# schema_mixer.net
KiCad netlist of a schematic drawn in Altium Designer
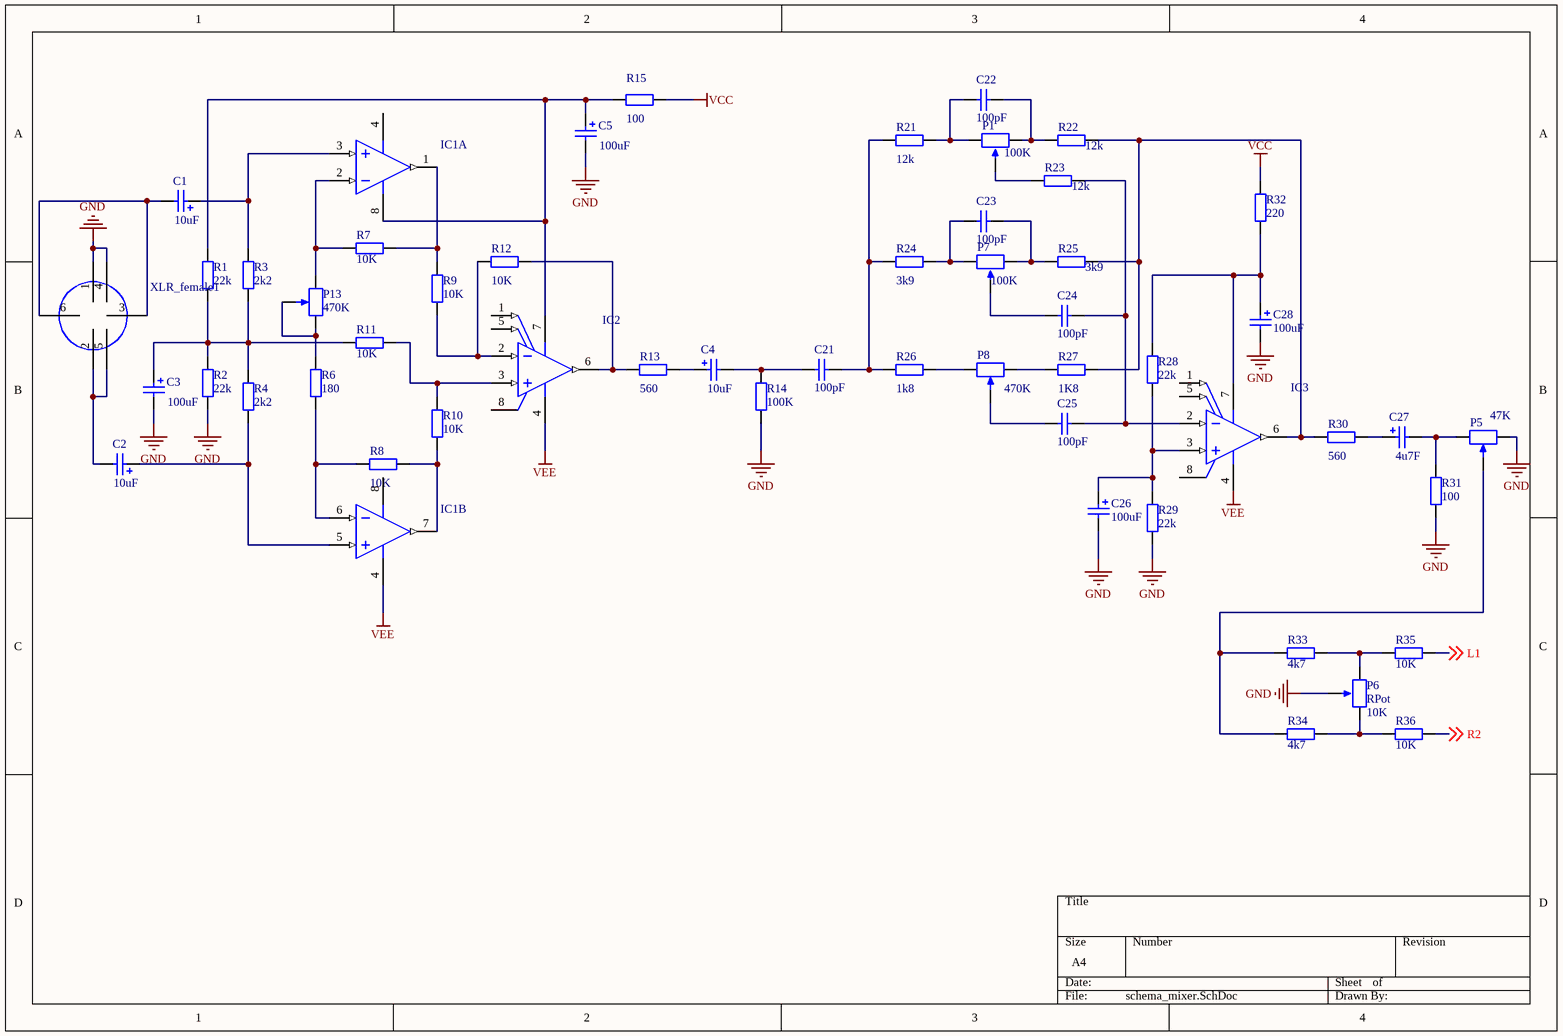
[diagram p0: schema_mixer.SchDoc]

(export (version "E")
  (design (tool "Eeschema 10.0.6"))
  (components
    (comp (ref "C1")
      (value "10uF")
      (footprint "POLAR0.8")
      (description "Polarized Capacitor (Axial)")
      (fields (field (name "Comment") "Cap Pol2") (field (name "PUBLISHER") "Altium Limited"))
      (libsource (lib "Miscellaneous Devices") (part "Cap Pol2"))
    )
    (comp (ref "C2")
      (value "10uF")
      (footprint "POLAR0.8")
      (description "Polarized Capacitor (Axial)")
      (fields (field (name "Comment") "Cap Pol2") (field (name "PUBLISHER") "Altium Limited"))
      (libsource (lib "Miscellaneous Devices") (part "Cap Pol2"))
    )
    (comp (ref "C3")
      (value "100uF")
      (footprint "POLAR0.8")
      (description "Polarized Capacitor (Axial)")
      (fields (field (name "Comment") "Cap Pol2") (field (name "PUBLISHER") "Altium Limited"))
      (libsource (lib "Miscellaneous Devices") (part "Cap Pol2"))
    )
    (comp (ref "C4")
      (value "10uF")
      (footprint "POLAR0.8")
      (description "Polarized Capacitor (Axial)")
      (fields (field (name "Comment") "Cap Pol2") (field (name "PUBLISHER") "Altium Limited"))
      (libsource (lib "Miscellaneous Devices") (part "Cap Pol2"))
    )
    (comp (ref "C5")
      (value "100uF")
      (footprint "POLAR0.8")
      (description "Polarized Capacitor (Axial)")
      (fields (field (name "Comment") "Cap Pol2") (field (name "PUBLISHER") "Altium Limited"))
      (libsource (lib "Miscellaneous Devices") (part "Cap Pol2"))
    )
    (comp (ref "C21")
      (value "100pF")
      (footprint "RAD-0.3")
      (description "Capacitor")
      (fields (field (name "Comment") "Cap") (field (name "PUBLISHER") "Altium Limited"))
      (libsource (lib "Autio_Mixer") (part "Cap"))
    )
    (comp (ref "C22")
      (value "100pF")
      (footprint "RAD-0.3")
      (description "Capacitor")
      (fields (field (name "Comment") "Cap") (field (name "PUBLISHER") "Altium Limited"))
      (libsource (lib "Autio_Mixer") (part "Cap"))
    )
    (comp (ref "C23")
      (value "100pF")
      (footprint "RAD-0.3")
      (description "Capacitor")
      (fields (field (name "Comment") "Cap") (field (name "PUBLISHER") "Altium Limited"))
      (libsource (lib "Autio_Mixer") (part "Cap"))
    )
    (comp (ref "C24")
      (value "100pF")
      (footprint "RAD-0.3")
      (description "Capacitor")
      (fields (field (name "Comment") "Cap") (field (name "PUBLISHER") "Altium Limited"))
      (libsource (lib "Autio_Mixer") (part "Cap"))
    )
    (comp (ref "C25")
      (value "100pF")
      (footprint "RAD-0.3")
      (description "Capacitor")
      (fields (field (name "Comment") "Cap") (field (name "PUBLISHER") "Altium Limited"))
      (libsource (lib "Autio_Mixer") (part "Cap"))
    )
    (comp (ref "C26")
      (value "100uF")
      (footprint "POLAR0.8")
      (description "Polarized Capacitor (Axial)")
      (fields (field (name "Comment") "Cap Pol2") (field (name "PUBLISHER") "Altium Limited"))
      (libsource (lib "Miscellaneous Devices") (part "Cap Pol2"))
    )
    (comp (ref "C27")
      (value "4u7F")
      (footprint "POLAR0.8")
      (description "Polarized Capacitor (Axial)")
      (fields (field (name "Comment") "Cap Pol2") (field (name "PUBLISHER") "Altium Limited"))
      (libsource (lib "Miscellaneous Devices") (part "Cap Pol2"))
    )
    (comp (ref "C28")
      (value "100uF")
      (footprint "POLAR0.8")
      (description "Polarized Capacitor (Axial)")
      (fields (field (name "Comment") "Cap Pol2") (field (name "PUBLISHER") "Altium Limited"))
      (libsource (lib "Miscellaneous Devices") (part "Cap Pol2"))
    )
    (comp (ref "IC1")
      (value "LM833DR2G")
      (footprint "OPAMP_LM833")
      (description "Low Noise, Audio Dual Operational Amplifier, -40 to 85 degC, 8-Pin SOIC, Pb-Free, Tape and Reel")
      (fields (field (name "MANUFACTURER") "On Semiconductor"))
      (libsource (lib "Autio_Mixer") (part "opamp_LM833"))
    )
    (comp (ref "IC2")
      (value "TL061CD")
      (footprint "OPAMP_TL061")
      (fields (field (name "MANUFACTURER") "Texas Instruments"))
      (libsource (lib "Autio_Mixer") (part "opamp_L061"))
    )
    (comp (ref "IC3")
      (value "TL061CD")
      (footprint "OPAMP_TL061")
      (fields (field (name "MANUFACTURER") "Texas Instruments"))
      (libsource (lib "Autio_Mixer") (part "opamp_TL061"))
    )
    (comp (ref "P1")
      (value "100K")
      (footprint "VR5")
      (description "Potentiometer")
      (fields (field (name "Comment") "RPot") (field (name "PUBLISHER") "Altium Limited"))
      (libsource (lib "") (part "RPot_1"))
    )
    (comp (ref "P5")
      (value "47K")
      (footprint "VR5")
      (description "Potentiometer")
      (fields (field (name "Comment") "RPot") (field (name "PUBLISHER") "Altium Limited"))
      (libsource (lib "") (part "RPot_1_1"))
    )
    (comp (ref "P6")
      (value "RPot")
      (footprint "VR5")
      (description "Potentiometer")
      (fields (field (name "ALTIUM_VALUE") "10K") (field (name "PUBLISHER") "Altium Limited"))
      (libsource (lib "Autio_Mixer") (part "RPot"))
    )
    (comp (ref "P7")
      (value "100K")
      (footprint "VR5")
      (description "Potentiometer")
      (fields (field (name "Comment") "RPot") (field (name "PUBLISHER") "Altium Limited"))
      (libsource (lib "") (part "RPot_1"))
    )
    (comp (ref "P8")
      (value "470K")
      (footprint "VR5")
      (description "Potentiometer")
      (fields (field (name "Comment") "RPot") (field (name "PUBLISHER") "Altium Limited"))
      (libsource (lib "") (part "RPot_1_1"))
    )
    (comp (ref "P13")
      (value "470K")
      (footprint "VR5")
      (description "Potentiometer")
      (fields (field (name "Comment") "RPot") (field (name "PUBLISHER") "Altium Limited"))
      (libsource (lib "Autio_Mixer") (part "RPot_1"))
    )
    (comp (ref "R1")
      (value "22k")
      (footprint "C1206")
      (description "Resistor")
      (fields (field (name "Comment") "Res2") (field (name "PUBLISHER") "Altium Limited"))
      (libsource (lib "") (part "Res2_1"))
    )
    (comp (ref "R2")
      (value "22k")
      (footprint "C1206")
      (description "Resistor")
      (fields (field (name "Comment") "Res2") (field (name "PUBLISHER") "Altium Limited"))
      (libsource (lib "") (part "Res2_1"))
    )
    (comp (ref "R3")
      (value "2k2")
      (footprint "C1206")
      (description "Resistor")
      (fields (field (name "Comment") "Res2") (field (name "PUBLISHER") "Altium Limited"))
      (libsource (lib "") (part "Res2_1"))
    )
    (comp (ref "R4")
      (value "2k2")
      (footprint "C1206")
      (description "Resistor")
      (fields (field (name "Comment") "Res2") (field (name "PUBLISHER") "Altium Limited"))
      (libsource (lib "") (part "Res2_1"))
    )
    (comp (ref "R6")
      (value "180")
      (footprint "C1206")
      (description "Resistor")
      (fields (field (name "Comment") "Res2") (field (name "PUBLISHER") "Altium Limited"))
      (libsource (lib "") (part "Res2_1"))
    )
    (comp (ref "R7")
      (value "10K")
      (footprint "C1206")
      (description "Resistor")
      (fields (field (name "Comment") "Res2") (field (name "PUBLISHER") "Altium Limited"))
      (libsource (lib "Miscellaneous Devices") (part "Res2"))
    )
    (comp (ref "R8")
      (value "10K")
      (footprint "C1206")
      (description "Resistor")
      (fields (field (name "Comment") "Res2") (field (name "PUBLISHER") "Altium Limited"))
      (libsource (lib "Miscellaneous Devices") (part "Res2"))
    )
    (comp (ref "R9")
      (value "10K")
      (footprint "C1206")
      (description "Resistor")
      (fields (field (name "Comment") "Res2") (field (name "PUBLISHER") "Altium Limited"))
      (libsource (lib "") (part "Res2_1"))
    )
    (comp (ref "R10")
      (value "10K")
      (footprint "C1206")
      (description "Resistor")
      (fields (field (name "Comment") "Res2") (field (name "PUBLISHER") "Altium Limited"))
      (libsource (lib "") (part "Res2_1"))
    )
    (comp (ref "R11")
      (value "10K")
      (footprint "C1206")
      (description "Resistor")
      (fields (field (name "Comment") "Res2") (field (name "PUBLISHER") "Altium Limited"))
      (libsource (lib "Miscellaneous Devices") (part "Res2"))
    )
    (comp (ref "R12")
      (value "10K")
      (footprint "C1206")
      (description "Resistor")
      (fields (field (name "Comment") "Res2") (field (name "PUBLISHER") "Altium Limited"))
      (libsource (lib "Miscellaneous Devices") (part "Res2"))
    )
    (comp (ref "R13")
      (value "560")
      (footprint "C1206")
      (description "Resistor")
      (fields (field (name "Comment") "Res2") (field (name "PUBLISHER") "Altium Limited"))
      (libsource (lib "Miscellaneous Devices") (part "Res2"))
    )
    (comp (ref "R14")
      (value "100K")
      (footprint "C1206")
      (description "Resistor")
      (fields (field (name "Comment") "Res2") (field (name "PUBLISHER") "Altium Limited"))
      (libsource (lib "") (part "Res2_1"))
    )
    (comp (ref "R15")
      (value "100")
      (footprint "C1206")
      (description "Resistor")
      (fields (field (name "Comment") "Res2") (field (name "PUBLISHER") "Altium Limited"))
      (libsource (lib "Miscellaneous Devices") (part "Res2"))
    )
    (comp (ref "R21")
      (value "12k")
      (footprint "C1206")
      (description "Resistor")
      (fields (field (name "Comment") "Res2") (field (name "PUBLISHER") "Altium Limited"))
      (libsource (lib "Miscellaneous Devices") (part "Res2"))
    )
    (comp (ref "R22")
      (value "12k")
      (footprint "C1206")
      (description "Resistor")
      (fields (field (name "Comment") "Res2") (field (name "PUBLISHER") "Altium Limited"))
      (libsource (lib "Miscellaneous Devices") (part "Res2"))
    )
    (comp (ref "R23")
      (value "12k")
      (footprint "C1206")
      (description "Resistor")
      (fields (field (name "Comment") "Res2") (field (name "PUBLISHER") "Altium Limited"))
      (libsource (lib "Miscellaneous Devices") (part "Res2"))
    )
    (comp (ref "R24")
      (value "3k9")
      (footprint "C1206")
      (description "Resistor")
      (fields (field (name "Comment") "Res2") (field (name "PUBLISHER") "Altium Limited"))
      (libsource (lib "Miscellaneous Devices") (part "Res2"))
    )
    (comp (ref "R25")
      (value "3k9")
      (footprint "C1206")
      (description "Resistor")
      (fields (field (name "Comment") "Res2") (field (name "PUBLISHER") "Altium Limited"))
      (libsource (lib "Miscellaneous Devices") (part "Res2"))
    )
    (comp (ref "R26")
      (value "1k8")
      (footprint "C1206")
      (description "Resistor")
      (fields (field (name "Comment") "Res2") (field (name "PUBLISHER") "Altium Limited"))
      (libsource (lib "Miscellaneous Devices") (part "Res2"))
    )
    (comp (ref "R27")
      (value "1K8")
      (footprint "C1206")
      (description "Resistor")
      (fields (field (name "Comment") "Res2") (field (name "PUBLISHER") "Altium Limited"))
      (libsource (lib "Miscellaneous Devices") (part "Res2"))
    )
    (comp (ref "R28")
      (value "22k")
      (footprint "C1206")
      (description "Resistor")
      (fields (field (name "Comment") "Res2") (field (name "PUBLISHER") "Altium Limited"))
      (libsource (lib "") (part "Res2_1"))
    )
    (comp (ref "R29")
      (value "22k")
      (footprint "C1206")
      (description "Resistor")
      (fields (field (name "Comment") "Res2") (field (name "PUBLISHER") "Altium Limited"))
      (libsource (lib "") (part "Res2_1"))
    )
    (comp (ref "R30")
      (value "560")
      (footprint "C1206")
      (description "Resistor")
      (fields (field (name "Comment") "Res2") (field (name "PUBLISHER") "Altium Limited"))
      (libsource (lib "Miscellaneous Devices") (part "Res2"))
    )
    (comp (ref "R31")
      (value "100")
      (footprint "C1206")
      (description "Resistor")
      (fields (field (name "Comment") "Res2") (field (name "PUBLISHER") "Altium Limited"))
      (libsource (lib "") (part "Res2_1"))
    )
    (comp (ref "R32")
      (value "220")
      (footprint "C1206")
      (description "Resistor")
      (fields (field (name "Comment") "Res2") (field (name "PUBLISHER") "Altium Limited"))
      (libsource (lib "") (part "Res2_1"))
    )
    (comp (ref "R33")
      (value "4k7")
      (footprint "C1206")
      (description "Resistor")
      (fields (field (name "Comment") "Res2") (field (name "PUBLISHER") "Altium Limited"))
      (libsource (lib "Autio_Mixer") (part "Res2_13"))
    )
    (comp (ref "R34")
      (value "4k7")
      (footprint "C1206")
      (description "Resistor")
      (fields (field (name "Comment") "Res2") (field (name "PUBLISHER") "Altium Limited"))
      (libsource (lib "Autio_Mixer") (part "Res2_13"))
    )
    (comp (ref "R35")
      (value "10K")
      (footprint "C1206")
      (description "Resistor")
      (fields (field (name "Comment") "Res2") (field (name "PUBLISHER") "Altium Limited"))
      (libsource (lib "Autio_Mixer") (part "Res2_3"))
    )
    (comp (ref "R36")
      (value "10K")
      (footprint "C1206")
      (description "Resistor")
      (fields (field (name "Comment") "Res2") (field (name "PUBLISHER") "Altium Limited"))
      (libsource (lib "Autio_Mixer") (part "Res2_3"))
    )
    (comp (ref "XLR_female1")
      (value "XLR_female")
      (footprint "XLR_Femail_Neutrik_NCJ6FA-V")
      (libsource (lib "Autio_Mixer") (part "XLR_female"))
    )
  )
  (nets
    (net (code "1") (name "GND") (class "Default")
      (node (ref "C26") (pin "2") (pinfunction "2_2") (pintype "passive"))
      (node (ref "C28") (pin "2") (pinfunction "2_2") (pintype "passive"))
      (node (ref "C3") (pin "2") (pinfunction "2_2") (pintype "passive"))
      (node (ref "C5") (pin "2") (pinfunction "2_2") (pintype "passive"))
      (node (ref "P5") (pin "2") (pinfunction "BOT_2") (pintype "passive"))
      (node (ref "P6") (pin "3") (pinfunction "TAP_3") (pintype "passive"))
      (node (ref "R14") (pin "1") (pinfunction "1_1") (pintype "passive"))
      (node (ref "R2") (pin "1") (pinfunction "1_1") (pintype "passive"))
      (node (ref "R29") (pin "1") (pinfunction "1_1") (pintype "passive"))
      (node (ref "R31") (pin "1") (pinfunction "1_1") (pintype "passive"))
      (node (ref "XLR_female1") (pin "1") (pinfunction "GND_1") (pintype "passive"))
      (node (ref "XLR_female1") (pin "4") (pinfunction "Sleeve_/_GND_4") (pintype "passive"))
    )
    (net (code "2") (name "L1") (class "Default")
      (node (ref "R35") (pin "2") (pinfunction "2_2") (pintype "passive"))
    )
    (net (code "3") (name "Net-(C3-Pad1)") (class "Default")
      (node (ref "C3") (pin "1") (pinfunction "1_1") (pintype "passive"))
      (node (ref "R1") (pin "1") (pinfunction "1_1") (pintype "passive"))
      (node (ref "R11") (pin "1") (pinfunction "1_1") (pintype "passive"))
      (node (ref "R2") (pin "2") (pinfunction "2_2") (pintype "passive"))
      (node (ref "R3") (pin "1") (pinfunction "1_1") (pintype "passive"))
      (node (ref "R4") (pin "2") (pinfunction "2_2") (pintype "passive"))
    )
    (net (code "4") (name "Net-(C4-Pad1)") (class "Default")
      (node (ref "C4") (pin "1") (pinfunction "1_1") (pintype "passive"))
      (node (ref "R13") (pin "2") (pinfunction "2_2") (pintype "passive"))
    )
    (net (code "5") (name "Net-(C21-Pad1)") (class "Default")
      (node (ref "C21") (pin "1") (pinfunction "1_1") (pintype "passive"))
      (node (ref "C4") (pin "2") (pinfunction "2_2") (pintype "passive"))
      (node (ref "R14") (pin "2") (pinfunction "2_2") (pintype "passive"))
    )
    (net (code "6") (name "Net-(C21-Pad2)") (class "Default")
      (node (ref "C21") (pin "2") (pinfunction "2_2") (pintype "passive"))
      (node (ref "R21") (pin "1") (pinfunction "1_1") (pintype "passive"))
      (node (ref "R24") (pin "1") (pinfunction "1_1") (pintype "passive"))
      (node (ref "R26") (pin "1") (pinfunction "1_1") (pintype "passive"))
    )
    (net (code "7") (name "Net-(C27-Pad1)") (class "Default")
      (node (ref "C27") (pin "1") (pinfunction "1_1") (pintype "passive"))
      (node (ref "R30") (pin "2") (pinfunction "2_2") (pintype "passive"))
    )
    (net (code "8") (name "Net-(IC1A-IN1+)") (class "Default")
      (node (ref "C1") (pin "1") (pinfunction "1_1") (pintype "passive"))
      (node (ref "IC1") (pin "3") (pinfunction "IN1+_3") (pintype "input"))
      (node (ref "R3") (pin "2") (pinfunction "2_2") (pintype "passive"))
    )
    (net (code "9") (name "Net-(IC1A-IN1-)") (class "Default")
      (node (ref "IC1") (pin "2") (pinfunction "IN1-_2") (pintype "input"))
      (node (ref "P13") (pin "1") (pinfunction "TOP_1") (pintype "passive"))
      (node (ref "R7") (pin "1") (pinfunction "1_1") (pintype "passive"))
    )
    (net (code "10") (name "Net-(IC1A-OUT1)") (class "Default")
      (node (ref "IC1") (pin "1") (pinfunction "OUT1_1") (pintype "output"))
      (node (ref "R7") (pin "2") (pinfunction "2_2") (pintype "passive"))
      (node (ref "R9") (pin "2") (pinfunction "2_2") (pintype "passive"))
    )
    (net (code "11") (name "Net-(IC1A-VCC)") (class "Default")
      (node (ref "C5") (pin "1") (pinfunction "1_1") (pintype "passive"))
      (node (ref "IC1") (pin "8") (pinfunction "VCC_8") (pintype "power_in"))
      (node (ref "IC2") (pin "7") (pinfunction "VCC+_7") (pintype "power_in"))
      (node (ref "R1") (pin "2") (pinfunction "2_2") (pintype "passive"))
      (node (ref "R15") (pin "1") (pinfunction "1_1") (pintype "passive"))
    )
    (net (code "12") (name "Net-(IC1B-IN2+)") (class "Default")
      (node (ref "C2") (pin "1") (pinfunction "1_1") (pintype "passive"))
      (node (ref "IC1") (pin "5") (pinfunction "IN2+_5") (pintype "input"))
      (node (ref "R4") (pin "1") (pinfunction "1_1") (pintype "passive"))
    )
    (net (code "13") (name "Net-(IC1B-IN2-)") (class "Default")
      (node (ref "IC1") (pin "6") (pinfunction "IN2-_6") (pintype "input"))
      (node (ref "R6") (pin "1") (pinfunction "1_1") (pintype "passive"))
      (node (ref "R8") (pin "1") (pinfunction "1_1") (pintype "passive"))
    )
    (net (code "14") (name "Net-(IC1B-OUT2)") (class "Default")
      (node (ref "IC1") (pin "7") (pinfunction "OUT2_7") (pintype "output"))
      (node (ref "R10") (pin "1") (pinfunction "1_1") (pintype "passive"))
      (node (ref "R8") (pin "2") (pinfunction "2_2") (pintype "passive"))
    )
    (net (code "15") (name "Net-(IC2-IN+)") (class "Default")
      (node (ref "IC2") (pin "3") (pinfunction "IN+_3") (pintype "input"))
      (node (ref "R10") (pin "2") (pinfunction "2_2") (pintype "passive"))
      (node (ref "R11") (pin "2") (pinfunction "2_2") (pintype "passive"))
    )
    (net (code "16") (name "Net-(IC2-IN-)") (class "Default")
      (node (ref "IC2") (pin "2") (pinfunction "IN-_2") (pintype "input"))
      (node (ref "R12") (pin "1") (pinfunction "1_1") (pintype "passive"))
      (node (ref "R9") (pin "1") (pinfunction "1_1") (pintype "passive"))
    )
    (net (code "17") (name "Net-(IC2-OUT)") (class "Default")
      (node (ref "IC2") (pin "6") (pinfunction "OUT_6") (pintype "output"))
      (node (ref "R12") (pin "2") (pinfunction "2_2") (pintype "passive"))
      (node (ref "R13") (pin "1") (pinfunction "1_1") (pintype "passive"))
    )
    (net (code "18") (name "Net-(IC3-IN+)") (class "Default")
      (node (ref "C26") (pin "1") (pinfunction "1_1") (pintype "passive"))
      (node (ref "IC3") (pin "3") (pinfunction "IN+_3") (pintype "input"))
      (node (ref "R28") (pin "1") (pinfunction "1_1") (pintype "passive"))
      (node (ref "R29") (pin "2") (pinfunction "2_2") (pintype "passive"))
    )
    (net (code "19") (name "Net-(IC3-IN-)") (class "Default")
      (node (ref "C24") (pin "2") (pinfunction "2_2") (pintype "passive"))
      (node (ref "C25") (pin "2") (pinfunction "2_2") (pintype "passive"))
      (node (ref "IC3") (pin "2") (pinfunction "IN-_2") (pintype "input"))
      (node (ref "R23") (pin "2") (pinfunction "2_2") (pintype "passive"))
    )
    (net (code "20") (name "Net-(IC3-OUT)") (class "Default")
      (node (ref "IC3") (pin "6") (pinfunction "OUT_6") (pintype "output"))
      (node (ref "R22") (pin "2") (pinfunction "2_2") (pintype "passive"))
      (node (ref "R25") (pin "2") (pinfunction "2_2") (pintype "passive"))
      (node (ref "R27") (pin "2") (pinfunction "2_2") (pintype "passive"))
      (node (ref "R30") (pin "1") (pinfunction "1_1") (pintype "passive"))
    )
    (net (code "21") (name "Net-(IC3-VCC+)") (class "Default")
      (node (ref "C28") (pin "1") (pinfunction "1_1") (pintype "passive"))
      (node (ref "IC3") (pin "7") (pinfunction "VCC+_7") (pintype "power_in"))
      (node (ref "R28") (pin "2") (pinfunction "2_2") (pintype "passive"))
      (node (ref "R32") (pin "1") (pinfunction "1_1") (pintype "passive"))
    )
    (net (code "22") (name "Net-(P1-BOT)") (class "Default")
      (node (ref "C22") (pin "2") (pinfunction "2_2") (pintype "passive"))
      (node (ref "P1") (pin "2") (pinfunction "BOT_2") (pintype "passive"))
      (node (ref "R22") (pin "1") (pinfunction "1_1") (pintype "passive"))
    )
    (net (code "23") (name "Net-(P1-TAP)") (class "Default")
      (node (ref "P1") (pin "3") (pinfunction "TAP_3") (pintype "passive"))
      (node (ref "R23") (pin "1") (pinfunction "1_1") (pintype "passive"))
    )
    (net (code "24") (name "Net-(P1-TOP)") (class "Default")
      (node (ref "C22") (pin "1") (pinfunction "1_1") (pintype "passive"))
      (node (ref "P1") (pin "1") (pinfunction "TOP_1") (pintype "passive"))
      (node (ref "R21") (pin "2") (pinfunction "2_2") (pintype "passive"))
    )
    (net (code "25") (name "Net-(P5-TAP)") (class "Default")
      (node (ref "P5") (pin "3") (pinfunction "TAP_3") (pintype "passive"))
      (node (ref "R33") (pin "1") (pinfunction "1_1") (pintype "passive"))
      (node (ref "R34") (pin "1") (pinfunction "1_1") (pintype "passive"))
    )
    (net (code "26") (name "Net-(P5-TOP)") (class "Default")
      (node (ref "C27") (pin "2") (pinfunction "2_2") (pintype "passive"))
      (node (ref "P5") (pin "1") (pinfunction "TOP_1") (pintype "passive"))
      (node (ref "R31") (pin "2") (pinfunction "2_2") (pintype "passive"))
    )
    (net (code "27") (name "Net-(P6-BOT)") (class "Default")
      (node (ref "P6") (pin "2") (pinfunction "BOT_2") (pintype "passive"))
      (node (ref "R34") (pin "2") (pinfunction "2_2") (pintype "passive"))
      (node (ref "R36") (pin "1") (pinfunction "1_1") (pintype "passive"))
    )
    (net (code "28") (name "Net-(P6-TOP)") (class "Default")
      (node (ref "P6") (pin "1") (pinfunction "TOP_1") (pintype "passive"))
      (node (ref "R33") (pin "2") (pinfunction "2_2") (pintype "passive"))
      (node (ref "R35") (pin "1") (pinfunction "1_1") (pintype "passive"))
    )
    (net (code "29") (name "Net-(P7-BOT)") (class "Default")
      (node (ref "C23") (pin "2") (pinfunction "2_2") (pintype "passive"))
      (node (ref "P7") (pin "2") (pinfunction "BOT_2") (pintype "passive"))
      (node (ref "R25") (pin "1") (pinfunction "1_1") (pintype "passive"))
    )
    (net (code "30") (name "Net-(P7-TAP)") (class "Default")
      (node (ref "C24") (pin "1") (pinfunction "1_1") (pintype "passive"))
      (node (ref "P7") (pin "3") (pinfunction "TAP_3") (pintype "passive"))
    )
    (net (code "31") (name "Net-(P7-TOP)") (class "Default")
      (node (ref "C23") (pin "1") (pinfunction "1_1") (pintype "passive"))
      (node (ref "P7") (pin "1") (pinfunction "TOP_1") (pintype "passive"))
      (node (ref "R24") (pin "2") (pinfunction "2_2") (pintype "passive"))
    )
    (net (code "32") (name "Net-(P8-BOT)") (class "Default")
      (node (ref "P8") (pin "2") (pinfunction "BOT_2") (pintype "passive"))
      (node (ref "R27") (pin "1") (pinfunction "1_1") (pintype "passive"))
    )
    (net (code "33") (name "Net-(P8-TAP)") (class "Default")
      (node (ref "C25") (pin "1") (pinfunction "1_1") (pintype "passive"))
      (node (ref "P8") (pin "3") (pinfunction "TAP_3") (pintype "passive"))
    )
    (net (code "34") (name "Net-(P8-TOP)") (class "Default")
      (node (ref "P8") (pin "1") (pinfunction "TOP_1") (pintype "passive"))
      (node (ref "R26") (pin "2") (pinfunction "2_2") (pintype "passive"))
    )
    (net (code "35") (name "Net-(P13-BOT)") (class "Default")
      (node (ref "P13") (pin "2") (pinfunction "BOT_2") (pintype "passive"))
      (node (ref "P13") (pin "3") (pinfunction "TAP_3") (pintype "passive"))
      (node (ref "R6") (pin "2") (pinfunction "2_2") (pintype "passive"))
    )
    (net (code "36") (name "Net-(XLR_female1-Pos)") (class "Default")
      (node (ref "C2") (pin "2") (pinfunction "2_2") (pintype "passive"))
      (node (ref "XLR_female1") (pin "2") (pinfunction "Pos_2") (pintype "passive"))
      (node (ref "XLR_female1") (pin "5") (pinfunction "Ring_/_neg_5") (pintype "passive"))
    )
    (net (code "37") (name "Net-(XLR_female1-Tip_{slash}_pos)") (class "Default")
      (node (ref "C1") (pin "2") (pinfunction "2_2") (pintype "passive"))
      (node (ref "XLR_female1") (pin "3") (pinfunction "negative_3") (pintype "passive"))
      (node (ref "XLR_female1") (pin "6") (pinfunction "Tip_/_pos_6") (pintype "passive"))
    )
    (net (code "38") (name "R2") (class "Default")
      (node (ref "R36") (pin "2") (pinfunction "2_2") (pintype "passive"))
    )
    (net (code "39") (name "VCC") (class "Default")
      (node (ref "R15") (pin "2") (pinfunction "2_2") (pintype "passive"))
      (node (ref "R32") (pin "2") (pinfunction "2_2") (pintype "passive"))
    )
    (net (code "40") (name "VEE") (class "Default")
      (node (ref "IC1") (pin "4") (pinfunction "VEE_4") (pintype "power_in"))
      (node (ref "IC2") (pin "4") (pinfunction "VCC-_4") (pintype "power_in"))
      (node (ref "IC3") (pin "4") (pinfunction "VCC-_4") (pintype "power_in"))
    )
    (net (code "41") (name "unconnected-(IC1A-VEE-Pad4)") (class "Default")
      (node (ref "IC1") (pin "4") (pinfunction "VEE_4") (pintype "power_in"))
    )
    (net (code "42") (name "unconnected-(IC1B-VCC-Pad8)") (class "Default")
      (node (ref "IC1") (pin "8") (pinfunction "VCC_8") (pintype "power_in"))
    )
    (net (code "43") (name "unconnected-(IC2-NC-Pad8)") (class "Default")
      (node (ref "IC2") (pin "8") (pinfunction "NC_8") (pintype "passive"))
    )
    (net (code "44") (name "unconnected-(IC2-OFFSET_N1-Pad1)") (class "Default")
      (node (ref "IC2") (pin "1") (pinfunction "OFFSET_N1_1") (pintype "input"))
    )
    (net (code "45") (name "unconnected-(IC2-OFFSET_N2-Pad5)") (class "Default")
      (node (ref "IC2") (pin "5") (pinfunction "OFFSET_N2_5") (pintype "input"))
    )
    (net (code "46") (name "unconnected-(IC3-NC-Pad8)") (class "Default")
      (node (ref "IC3") (pin "8") (pinfunction "NC_8") (pintype "passive"))
    )
    (net (code "47") (name "unconnected-(IC3-OFFSET_N1-Pad1)") (class "Default")
      (node (ref "IC3") (pin "1") (pinfunction "OFFSET_N1_1") (pintype "input"))
    )
    (net (code "48") (name "unconnected-(IC3-OFFSET_N2-Pad5)") (class "Default")
      (node (ref "IC3") (pin "5") (pinfunction "OFFSET_N2_5") (pintype "input"))
    )
  )
)
